# RCMETER.net
KiCad netlist of a schematic drawn in EAGLE
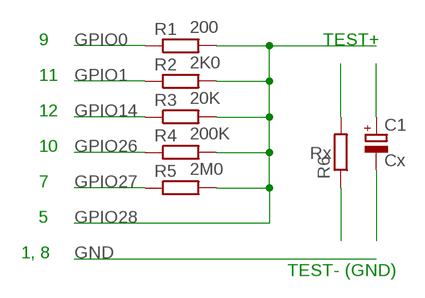
[diagram p0: schematic, sheet 1]

(export (version "E")
  (design (tool "Eeschema 10.0.6"))
  (components
    (comp (ref "C1")
      (value "Cx")
      (footprint "eagle-import:B45181B")
      (libsource (lib "eagle-import") (part "CPOL-EUB45181B"))
    )
    (comp (ref "R1")
      (value "200")
      (footprint "eagle-import:0204_7")
      (libsource (lib "eagle-import") (part "R-EU_0204/7"))
    )
    (comp (ref "R2")
      (value "2K0")
      (footprint "eagle-import:0204_7")
      (libsource (lib "eagle-import") (part "R-EU_0204/7"))
    )
    (comp (ref "R3")
      (value "20K")
      (footprint "eagle-import:0204_7")
      (libsource (lib "eagle-import") (part "R-EU_0204/7"))
    )
    (comp (ref "R4")
      (value "200K")
      (footprint "eagle-import:0204_7")
      (libsource (lib "eagle-import") (part "R-EU_0204/7"))
    )
    (comp (ref "R5")
      (value "2M0")
      (footprint "eagle-import:0204_7")
      (libsource (lib "eagle-import") (part "R-EU_0204/7"))
    )
    (comp (ref "R6")
      (value "Rx")
      (footprint "eagle-import:0204_7")
      (libsource (lib "eagle-import") (part "R-EU_0204/7"))
    )
  )
  (nets
    (net (code "2") (name "/GPIO0") (class "Default")
      (node (ref "R1") (pin "1") (pinfunction "1_1") (pintype "passive"))
    )
    (net (code "3") (name "/GPIO1") (class "Default")
      (node (ref "R2") (pin "1") (pinfunction "1_1") (pintype "passive"))
    )
    (net (code "4") (name "/GPIO14") (class "Default")
      (node (ref "R3") (pin "1") (pinfunction "1_1") (pintype "passive"))
    )
    (net (code "5") (name "/GPIO26") (class "Default")
      (node (ref "R4") (pin "1") (pinfunction "1_1") (pintype "passive"))
    )
    (net (code "6") (name "/GPIO27") (class "Default")
      (node (ref "R5") (pin "1") (pinfunction "1_1") (pintype "passive"))
    )
    (net (code "7") (name "/GPIO28") (class "Default")
      (node (ref "R1") (pin "2") (pinfunction "2_2") (pintype "passive"))
      (node (ref "R2") (pin "2") (pinfunction "2_2") (pintype "passive"))
      (node (ref "R3") (pin "2") (pinfunction "2_2") (pintype "passive"))
      (node (ref "R4") (pin "2") (pinfunction "2_2") (pintype "passive"))
      (node (ref "R5") (pin "2") (pinfunction "2_2") (pintype "passive"))
    )
    (net (code "8") (name "unconnected-(C1-Pad+)") (class "Default")
      (node (ref "C1") (pin "+") (pinfunction "+_+") (pintype "passive"))
    )
    (net (code "9") (name "unconnected-(C1-Pad-)") (class "Default")
      (node (ref "C1") (pin "-") (pinfunction "-_-") (pintype "passive"))
    )
    (net (code "10") (name "unconnected-(R6-Pad1)") (class "Default")
      (node (ref "R6") (pin "1") (pinfunction "1_1") (pintype "passive"))
    )
    (net (code "11") (name "unconnected-(R6-Pad2)") (class "Default")
      (node (ref "R6") (pin "2") (pinfunction "2_2") (pintype "passive"))
    )
  )
)
